# spider_mx8_thin.net
KiCad netlist of a schematic drawn in EAGLE
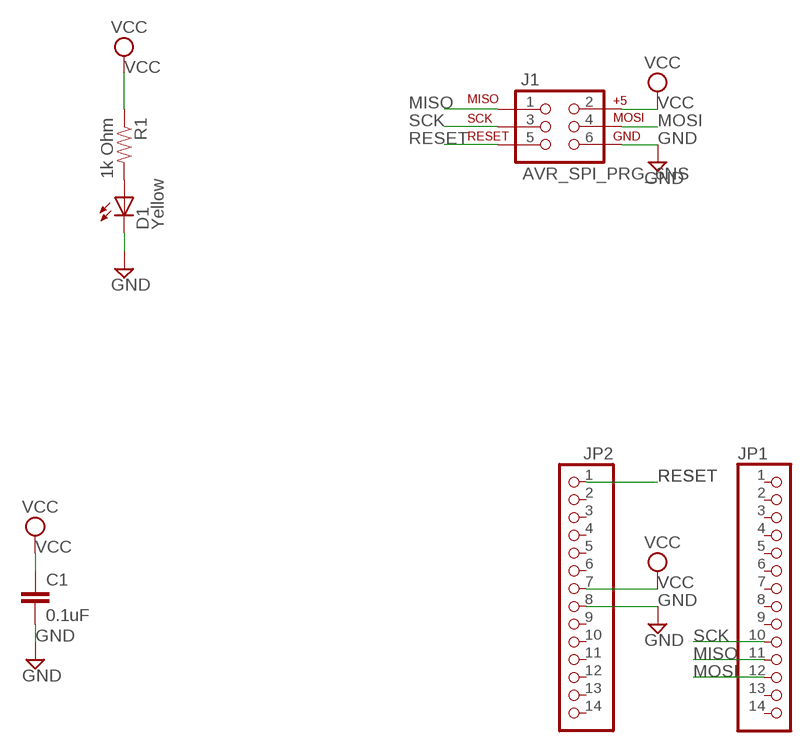
[diagram p0: schematic, sheet 1]

(export (version "E")
  (design (tool "Eeschema 10.0.6"))
  (components
    (comp (ref "C1")
      (value "0.1uF")
      (footprint "eagle-import:1206")
      (libsource (lib "eagle-import") (part "CAP1206"))
    )
    (comp (ref "D1")
      (value "Yellow")
      (footprint "eagle-import:LED-1206")
      (libsource (lib "eagle-import") (part "LED-YELLOWLILYPAD"))
    )
    (comp (ref "J1")
      (value "AVR_SPI_PRG_6NS")
      (footprint "eagle-import:2X3-NS")
      (libsource (lib "eagle-import") (part "AVR_SPI_PRG_6NS"))
    )
    (comp (ref "JP1")
      (value "PINHD-1X14")
      (footprint "eagle-import:1X14")
      (libsource (lib "eagle-import") (part "PINHD-1X14"))
    )
    (comp (ref "JP2")
      (value "PINHD-1X14")
      (footprint "eagle-import:1X14")
      (libsource (lib "eagle-import") (part "PINHD-1X14"))
    )
    (comp (ref "R1")
      (value "1k Ohm")
      (footprint "eagle-import:1206")
      (libsource (lib "eagle-import") (part "RESISTOR1206"))
    )
  )
  (nets
    (net (code "1") (name "/MISO") (class "Default")
      (node (ref "J1") (pin "1") (pinfunction "1_1") (pintype "passive"))
      (node (ref "JP1") (pin "11") (pinfunction "11_11") (pintype "passive"))
    )
    (net (code "2") (name "/MOSI") (class "Default")
      (node (ref "J1") (pin "4") (pinfunction "4_4") (pintype "passive"))
      (node (ref "JP1") (pin "12") (pinfunction "12_12") (pintype "passive"))
    )
    (net (code "3") (name "/RESET") (class "Default")
      (node (ref "J1") (pin "5") (pinfunction "5_5") (pintype "passive"))
      (node (ref "JP2") (pin "1") (pinfunction "1_1") (pintype "passive"))
    )
    (net (code "4") (name "/SCK") (class "Default")
      (node (ref "J1") (pin "3") (pinfunction "3_3") (pintype "passive"))
      (node (ref "JP1") (pin "10") (pinfunction "10_10") (pintype "passive"))
    )
    (net (code "5") (name "GND") (class "Default")
      (node (ref "C1") (pin "2") (pinfunction "2_2") (pintype "passive"))
      (node (ref "D1") (pin "C") (pinfunction "C_C") (pintype "passive"))
      (node (ref "J1") (pin "6") (pinfunction "6_6") (pintype "passive"))
      (node (ref "JP2") (pin "8") (pinfunction "8_8") (pintype "passive"))
    )
    (net (code "6") (name "Net-(D1-PadA)") (class "Default")
      (node (ref "D1") (pin "A") (pinfunction "A_A") (pintype "passive"))
      (node (ref "R1") (pin "2") (pinfunction "2_2") (pintype "passive"))
    )
    (net (code "7") (name "VCC") (class "Default")
      (node (ref "C1") (pin "1") (pinfunction "1_1") (pintype "passive"))
      (node (ref "J1") (pin "2") (pinfunction "2_2") (pintype "passive"))
      (node (ref "JP2") (pin "7") (pinfunction "7_7") (pintype "passive"))
      (node (ref "R1") (pin "1") (pinfunction "1_1") (pintype "passive"))
    )
    (net (code "8") (name "unconnected-(JP1-Pad1)") (class "Default")
      (node (ref "JP1") (pin "1") (pinfunction "1_1") (pintype "passive"))
    )
    (net (code "9") (name "unconnected-(JP1-Pad2)") (class "Default")
      (node (ref "JP1") (pin "2") (pinfunction "2_2") (pintype "passive"))
    )
    (net (code "10") (name "unconnected-(JP1-Pad3)") (class "Default")
      (node (ref "JP1") (pin "3") (pinfunction "3_3") (pintype "passive"))
    )
    (net (code "11") (name "unconnected-(JP1-Pad4)") (class "Default")
      (node (ref "JP1") (pin "4") (pinfunction "4_4") (pintype "passive"))
    )
    (net (code "12") (name "unconnected-(JP1-Pad5)") (class "Default")
      (node (ref "JP1") (pin "5") (pinfunction "5_5") (pintype "passive"))
    )
    (net (code "13") (name "unconnected-(JP1-Pad6)") (class "Default")
      (node (ref "JP1") (pin "6") (pinfunction "6_6") (pintype "passive"))
    )
    (net (code "14") (name "unconnected-(JP1-Pad7)") (class "Default")
      (node (ref "JP1") (pin "7") (pinfunction "7_7") (pintype "passive"))
    )
    (net (code "15") (name "unconnected-(JP1-Pad8)") (class "Default")
      (node (ref "JP1") (pin "8") (pinfunction "8_8") (pintype "passive"))
    )
    (net (code "16") (name "unconnected-(JP1-Pad9)") (class "Default")
      (node (ref "JP1") (pin "9") (pinfunction "9_9") (pintype "passive"))
    )
    (net (code "17") (name "unconnected-(JP1-Pad13)") (class "Default")
      (node (ref "JP1") (pin "13") (pinfunction "13_13") (pintype "passive"))
    )
    (net (code "18") (name "unconnected-(JP1-Pad14)") (class "Default")
      (node (ref "JP1") (pin "14") (pinfunction "14_14") (pintype "passive"))
    )
    (net (code "19") (name "unconnected-(JP2-Pad2)") (class "Default")
      (node (ref "JP2") (pin "2") (pinfunction "2_2") (pintype "passive"))
    )
    (net (code "20") (name "unconnected-(JP2-Pad3)") (class "Default")
      (node (ref "JP2") (pin "3") (pinfunction "3_3") (pintype "passive"))
    )
    (net (code "21") (name "unconnected-(JP2-Pad4)") (class "Default")
      (node (ref "JP2") (pin "4") (pinfunction "4_4") (pintype "passive"))
    )
    (net (code "22") (name "unconnected-(JP2-Pad5)") (class "Default")
      (node (ref "JP2") (pin "5") (pinfunction "5_5") (pintype "passive"))
    )
    (net (code "23") (name "unconnected-(JP2-Pad6)") (class "Default")
      (node (ref "JP2") (pin "6") (pinfunction "6_6") (pintype "passive"))
    )
    (net (code "24") (name "unconnected-(JP2-Pad9)") (class "Default")
      (node (ref "JP2") (pin "9") (pinfunction "9_9") (pintype "passive"))
    )
    (net (code "25") (name "unconnected-(JP2-Pad10)") (class "Default")
      (node (ref "JP2") (pin "10") (pinfunction "10_10") (pintype "passive"))
    )
    (net (code "26") (name "unconnected-(JP2-Pad11)") (class "Default")
      (node (ref "JP2") (pin "11") (pinfunction "11_11") (pintype "passive"))
    )
    (net (code "27") (name "unconnected-(JP2-Pad12)") (class "Default")
      (node (ref "JP2") (pin "12") (pinfunction "12_12") (pintype "passive"))
    )
    (net (code "28") (name "unconnected-(JP2-Pad13)") (class "Default")
      (node (ref "JP2") (pin "13") (pinfunction "13_13") (pintype "passive"))
    )
    (net (code "29") (name "unconnected-(JP2-Pad14)") (class "Default")
      (node (ref "JP2") (pin "14") (pinfunction "14_14") (pintype "passive"))
    )
  )
)
